# ESP8266-PIR.net
KiCad netlist of a schematic drawn in EAGLE
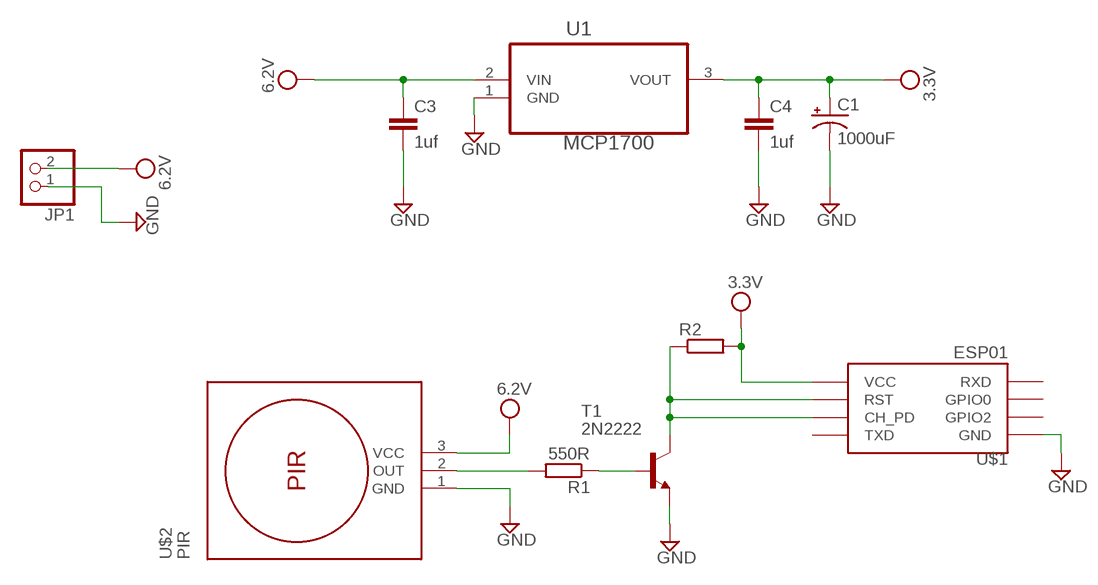
[diagram p0: schematic, sheet 1]

(export (version "E")
  (design (tool "Eeschema 10.0.6"))
  (components
    (comp (ref "C1")
      (value "1000uF")
      (footprint "eagle-import:CPOL-RADIAL-1000UF-25V")
      (libsource (lib "eagle-import") (part "CAP_POLPTH4"))
    )
    (comp (ref "C3")
      (value "1uf")
      (footprint "eagle-import:CAP-PTH-SMALLEZ")
      (libsource (lib "eagle-import") (part "CAPEZ"))
    )
    (comp (ref "C4")
      (value "1uf")
      (footprint "eagle-import:CAP-PTH-SMALLEZ")
      (libsource (lib "eagle-import") (part "CAPEZ"))
    )
    (comp (ref "JP1")
      (value "PINHD-1X2")
      (footprint "eagle-import:1X02")
      (libsource (lib "eagle-import") (part "PINHD-1X2"))
    )
    (comp (ref "R1")
      (value "550R")
      (footprint "eagle-import:0207_15")
      (libsource (lib "eagle-import") (part "R-EU_0207/15"))
    )
    (comp (ref "R2")
      (value "R-EU_0207/15")
      (footprint "eagle-import:0207_15")
      (libsource (lib "eagle-import") (part "R-EU_0207/15"))
    )
    (comp (ref "T1")
      (value "2N2222")
      (footprint "eagle-import:TO18")
      (libsource (lib "eagle-import") (part "2N2222"))
    )
    (comp (ref "U$1")
      (value "ESP01")
      (footprint "eagle-import:ESP01")
      (libsource (lib "eagle-import") (part "ESP01"))
    )
    (comp (ref "U$2")
      (value "PIR")
      (footprint "eagle-import:MOTION-PIR-DYP-ME003")
      (libsource (lib "eagle-import") (part "MOTION-PIR-DYP-ME003"))
    )
    (comp (ref "U1")
      (value "MCP1700")
      (footprint "eagle-import:TO127P254X495-3")
      (fields (field (name "MPN") "MCP1700-3302E/TO"))
      (libsource (lib "eagle-import") (part "MCP1700-3302E/TO"))
    )
  )
  (nets
    (net (code "1") (name "3.3V") (class "Default")
      (node (ref "C1") (pin "+") (pinfunction "+_+") (pintype "passive"))
      (node (ref "C4") (pin "1") (pinfunction "1_1") (pintype "passive"))
      (node (ref "R2") (pin "2") (pinfunction "2_2") (pintype "passive"))
      (node (ref "U$1") (pin "VCC") (pinfunction "VCC_VCC") (pintype "bidirectional"))
      (node (ref "U1") (pin "3") (pinfunction "VOUT_3") (pintype "output"))
    )
    (net (code "2") (name "6.2V") (class "Default")
      (node (ref "C3") (pin "1") (pinfunction "1_1") (pintype "passive"))
      (node (ref "JP1") (pin "2") (pinfunction "2_2") (pintype "passive"))
      (node (ref "U$2") (pin "3") (pinfunction "VCC_3") (pintype "power_in"))
      (node (ref "U1") (pin "2") (pinfunction "VIN_2") (pintype "input"))
    )
    (net (code "3") (name "GND") (class "Default")
      (node (ref "C1") (pin "-") (pinfunction "-_-") (pintype "passive"))
      (node (ref "C3") (pin "2") (pinfunction "2_2") (pintype "passive"))
      (node (ref "C4") (pin "2") (pinfunction "2_2") (pintype "passive"))
      (node (ref "JP1") (pin "1") (pinfunction "1_1") (pintype "passive"))
      (node (ref "T1") (pin "1") (pinfunction "E_1") (pintype "passive"))
      (node (ref "U$1") (pin "GND") (pinfunction "GND_GND") (pintype "bidirectional"))
      (node (ref "U$2") (pin "1") (pinfunction "GND_1") (pintype "power_in"))
      (node (ref "U1") (pin "1") (pinfunction "GND_1") (pintype "passive"))
    )
    (net (code "4") (name "Net-(T1-B)") (class "Default")
      (node (ref "R1") (pin "1") (pinfunction "1_1") (pintype "passive"))
      (node (ref "T1") (pin "2") (pinfunction "B_2") (pintype "passive"))
    )
    (net (code "5") (name "Net-(T1-C)") (class "Default")
      (node (ref "R2") (pin "1") (pinfunction "1_1") (pintype "passive"))
      (node (ref "T1") (pin "3") (pinfunction "C_3") (pintype "passive"))
      (node (ref "U$1") (pin "CH_PD") (pinfunction "CH_PD_CH_PD") (pintype "bidirectional"))
      (node (ref "U$1") (pin "RST") (pinfunction "RST_RST") (pintype "bidirectional"))
    )
    (net (code "6") (name "Net-(U$2-OUT)") (class "Default")
      (node (ref "R1") (pin "2") (pinfunction "2_2") (pintype "passive"))
      (node (ref "U$2") (pin "2") (pinfunction "OUT_2") (pintype "output"))
    )
    (net (code "7") (name "unconnected-(U$1-PadGPIO0)") (class "Default")
      (node (ref "U$1") (pin "GPIO0") (pinfunction "GPIO0_GPIO0") (pintype "bidirectional"))
    )
    (net (code "8") (name "unconnected-(U$1-PadGPIO2)") (class "Default")
      (node (ref "U$1") (pin "GPIO2") (pinfunction "GPIO2_GPIO2") (pintype "bidirectional"))
    )
    (net (code "9") (name "unconnected-(U$1-RXD-PadRX)") (class "Default")
      (node (ref "U$1") (pin "RX") (pinfunction "RXD_RX") (pintype "bidirectional"))
    )
    (net (code "10") (name "unconnected-(U$1-TXD-PadTX)") (class "Default")
      (node (ref "U$1") (pin "TX") (pinfunction "TXD_TX") (pintype "bidirectional"))
    )
  )
)
